# pulsePreamplifier.net
KiCad netlist of a schematic drawn in Altium Designer
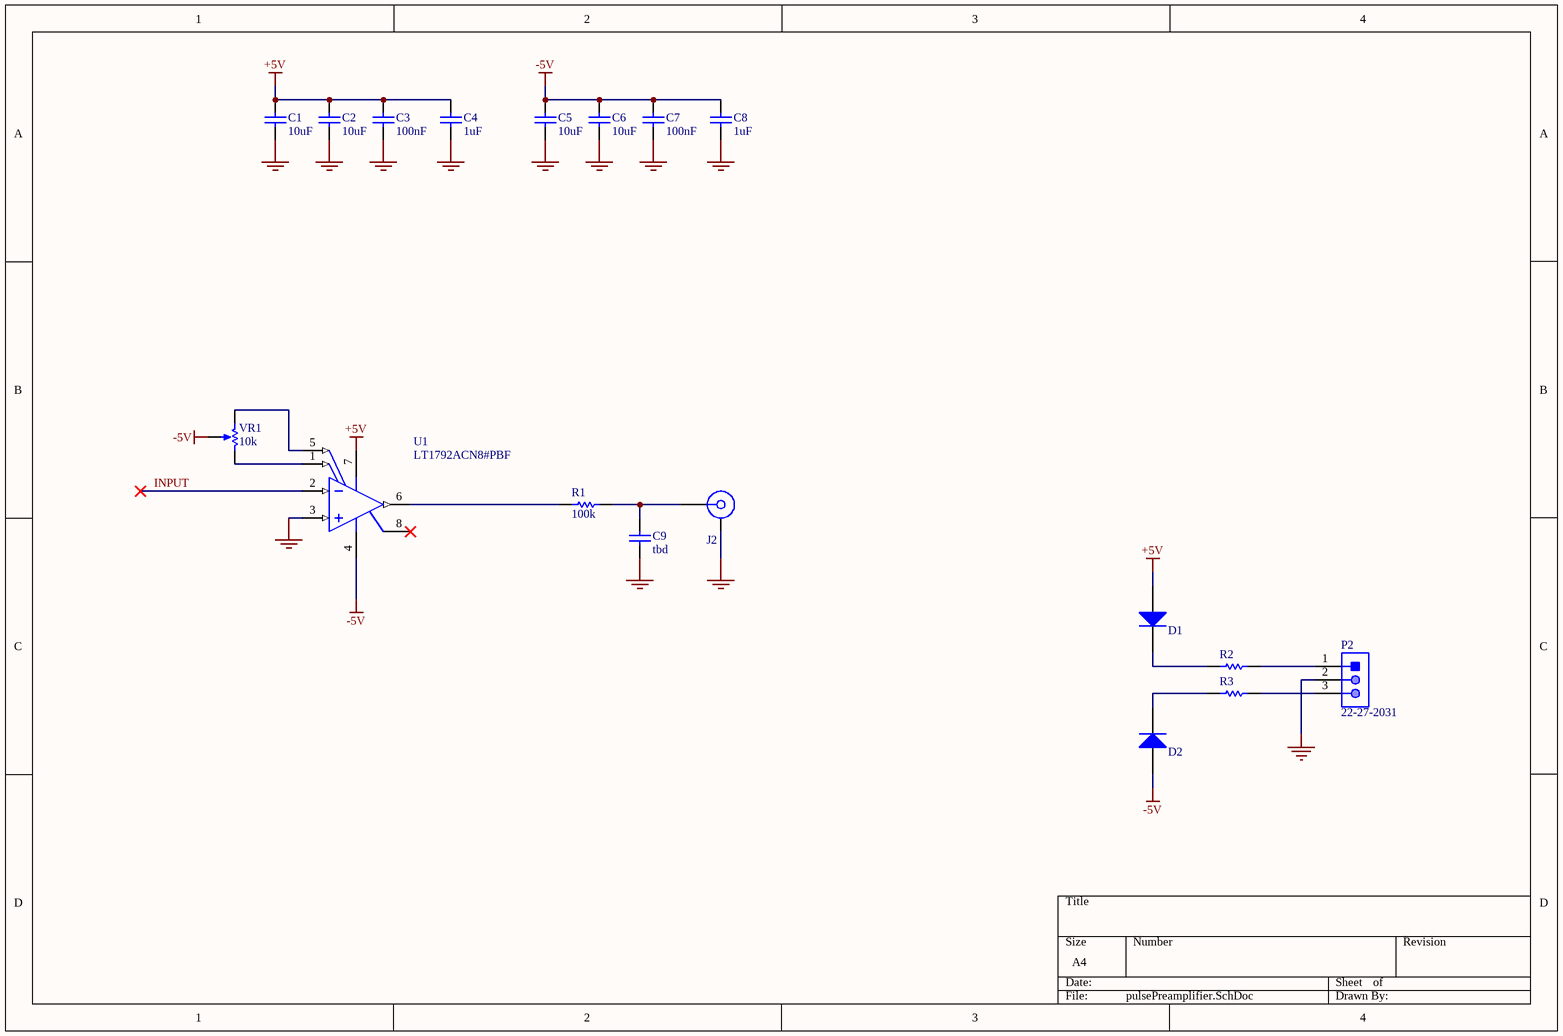
[diagram p0: pulsePreamplifier.SchDoc]

(export (version "E")
  (design (tool "Eeschema 10.0.6"))
  (components
    (comp (ref "C1")
      (value "10uF")
      (footprint "CAPC1206(3216)130_L")
      (description "CAP 10uF 10V -20% to +80% 1206 (3216 Metric) Thickness 1.3mm SMD")
      (fields (field (name "TOLERANCE") "-20% to +80%"))
      (libsource (lib "Altium Content Vault") (part "CAP"))
    )
    (comp (ref "C2")
      (value "10uF")
      (footprint "CAPC1206(3216)130_L")
      (description "CAP 10uF 10V -20% to +80% 1206 (3216 Metric) Thickness 1.3mm SMD")
      (fields (field (name "TOLERANCE") "-20% to +80%"))
      (libsource (lib "Altium Content Vault") (part "CAP"))
    )
    (comp (ref "C3")
      (value "100nF")
      (footprint "CAPC0603(1608)100_N")
      (description "CAP 100nF 25V ±20% 0603 (1608 Metric) Thickness 1mm SMD")
      (fields (field (name "TOLERANCE") "Â±20%"))
      (libsource (lib "Altium Content Vault") (part "CAP"))
    )
    (comp (ref "C4")
      (value "1uF")
      (footprint "CAPC0603(1608)100_N")
      (description "CAP 1uF 25V ±20% 0603 (1608 Metric) Thickness 1mm SMD")
      (fields (field (name "TOLERANCE") "Â±20%"))
      (libsource (lib "Altium Content Vault") (part "CAP"))
    )
    (comp (ref "C5")
      (value "10uF")
      (footprint "CAPC1206(3216)130_L")
      (description "CAP 10uF 10V -20% to +80% 1206 (3216 Metric) Thickness 1.3mm SMD")
      (fields (field (name "TOLERANCE") "-20% to +80%"))
      (libsource (lib "Altium Content Vault") (part "CAP"))
    )
    (comp (ref "C6")
      (value "10uF")
      (footprint "CAPC1206(3216)130_L")
      (description "CAP 10uF 10V -20% to +80% 1206 (3216 Metric) Thickness 1.3mm SMD")
      (fields (field (name "TOLERANCE") "-20% to +80%"))
      (libsource (lib "Altium Content Vault") (part "CAP"))
    )
    (comp (ref "C7")
      (value "100nF")
      (footprint "CAPC0603(1608)100_N")
      (description "CAP 100nF 25V ±20% 0603 (1608 Metric) Thickness 1mm SMD")
      (fields (field (name "TOLERANCE") "Â±20%"))
      (libsource (lib "Altium Content Vault") (part "CAP"))
    )
    (comp (ref "C8")
      (value "1uF")
      (footprint "CAPC0603(1608)100_N")
      (description "CAP 1uF 25V ±20% 0603 (1608 Metric) Thickness 1mm SMD")
      (fields (field (name "TOLERANCE") "Â±20%"))
      (libsource (lib "Altium Content Vault") (part "CAP"))
    )
    (comp (ref "C9")
      (value "tbd")
      (footprint "CAPC0603(1608)100_N")
      (description "CAP 1uF 25V ±20% 0603 (1608 Metric) Thickness 1mm SMD")
      (fields (field (name "TOLERANCE") "Â±20%"))
      (libsource (lib "Altium Content Vault") (part "CAP"))
    )
    (comp (ref "D1")
      (value "MMSD4148T3G")
      (footprint "ONSC-SOD123-2-425G-04_V")
      (description "Switching Diode, 100 V, 200 mA, -55 to 150 degC, 2-Pin SOD123 (425), RoHS, Tape and Reel")
      (fields (field (name "MANUFACTURER") "ON Semiconductor"))
      (libsource (lib "Altium Content Vault") (part "ONSC-MMSD4148-SOD123-2"))
    )
    (comp (ref "D2")
      (value "MMSD4148T3G")
      (footprint "ONSC-SOD123-2-425G-04_V")
      (description "Switching Diode, 100 V, 200 mA, -55 to 150 degC, 2-Pin SOD123 (425), RoHS, Tape and Reel")
      (fields (field (name "MANUFACTURER") "ON Semiconductor"))
      (libsource (lib "Altium Content Vault") (part "ONSC-MMSD4148-SOD123-2"))
    )
    (comp (ref "J2")
      (value "32K145-400L5")
      (footprint "ROS-32K145-400L5_V")
      (description "SMA Right Angle Jack, Edge Mount, Up to 18 GHz, -55 to 155 degC")
      (fields (field (name "MANUFACTURER") "Rosenberger"))
      (libsource (lib "Altium Content Vault") (part "ROS-CN-1F-RF1-A"))
    )
    (comp (ref "P2")
      (value "22-27-2031")
      (footprint "MOLX-22-27-2031_V")
      (fields (field (name "MANUFACTURER") "Molex"))
      (libsource (lib "Altium Content Vault") (part "CN-1P-M-R3"))
    )
    (comp (ref "R1")
      (value "100k")
      (footprint "RESC0805(2012)_L")
      (fields (field (name "TOLERANCE") "1 %") (field (name "POWER") "0.125 W"))
      (libsource (lib "Altium Content Vault") (part "RES"))
    )
    (comp (ref "R2")
      (value "100k")
      (footprint "RESC0603(1608)_N")
      (description "100R 0.1W 1% 0603 (1608 Metric)  SMD")
      (fields (field (name "TOLERANCE") "1 %") (field (name "POWER") "0.1 W"))
      (libsource (lib "Altium Content Vault") (part "RES"))
    )
    (comp (ref "R3")
      (value "100k")
      (footprint "RESC0603(1608)_N")
      (description "100R 0.1W 1% 0603 (1608 Metric)  SMD")
      (fields (field (name "TOLERANCE") "1 %") (field (name "POWER") "0.1 W"))
      (libsource (lib "Altium Content Vault") (part "RES"))
    )
    (comp (ref "U1")
      (value "LT1792ACN8#PBF")
      (footprint "LT-N8-8")
      (fields
        (field (name "MANUFACTURER") "Linear Technology")
        (field (name "LINEAR TECHNOLOGY PART NUMBER") "LT1792")
      )
      (libsource (lib "Altium Content Vault") (part "LT-LT1792-N8-8"))
    )
    (comp (ref "VR1")
      (value "10k")
      (footprint "BOUR-3362P")
      (description "Square Trimpot(R) Trimming Potentiometer, 10 KOhm, 300 V, -55 to 125 degC, 3-Pin THD, RoHS, Tube")
      (fields (field (name "TOLERANCE") "1%"))
      (libsource (lib "Altium Content Vault") (part "RES-POT-3"))
    )
  )
  (nets
    (net (code "1") (name "+5V") (class "Default")
      (node (ref "C1") (pin "2") (pinfunction "2_2") (pintype "passive"))
      (node (ref "C2") (pin "2") (pinfunction "2_2") (pintype "passive"))
      (node (ref "C3") (pin "2") (pinfunction "2_2") (pintype "passive"))
      (node (ref "C4") (pin "2") (pinfunction "2_2") (pintype "passive"))
      (node (ref "D1") (pin "2") (pinfunction "ANODE_2") (pintype "passive"))
      (node (ref "U1") (pin "7") (pinfunction "V+_7") (pintype "power_in"))
    )
    (net (code "2") (name "-5V") (class "Default")
      (node (ref "C5") (pin "2") (pinfunction "2_2") (pintype "passive"))
      (node (ref "C6") (pin "2") (pinfunction "2_2") (pintype "passive"))
      (node (ref "C7") (pin "2") (pinfunction "2_2") (pintype "passive"))
      (node (ref "C8") (pin "2") (pinfunction "2_2") (pintype "passive"))
      (node (ref "D2") (pin "2") (pinfunction "ANODE_2") (pintype "passive"))
      (node (ref "U1") (pin "4") (pinfunction "V-_4") (pintype "power_in"))
      (node (ref "VR1") (pin "2") (pinfunction "S_2") (pintype "passive"))
    )
    (net (code "3") (name "/INPUT") (class "Default")
      (node (ref "U1") (pin "2") (pinfunction "-IN_A_2") (pintype "input+no_connect"))
    )
    (net (code "4") (name "GND") (class "Default")
      (node (ref "C1") (pin "1") (pinfunction "1_1") (pintype "passive"))
      (node (ref "C2") (pin "1") (pinfunction "1_1") (pintype "passive"))
      (node (ref "C3") (pin "1") (pinfunction "1_1") (pintype "passive"))
      (node (ref "C4") (pin "1") (pinfunction "1_1") (pintype "passive"))
      (node (ref "C5") (pin "1") (pinfunction "1_1") (pintype "passive"))
      (node (ref "C6") (pin "1") (pinfunction "1_1") (pintype "passive"))
      (node (ref "C7") (pin "1") (pinfunction "1_1") (pintype "passive"))
      (node (ref "C8") (pin "1") (pinfunction "1_1") (pintype "passive"))
      (node (ref "C9") (pin "2") (pinfunction "2_2") (pintype "passive"))
      (node (ref "J2") (pin "MP") (pinfunction "MP_MP") (pintype "passive"))
      (node (ref "P2") (pin "2") (pinfunction "2_2") (pintype "passive"))
      (node (ref "U1") (pin "3") (pinfunction "+IN_A_3") (pintype "input"))
    )
    (net (code "5") (name "Net-(C9-Pad1)") (class "Default")
      (node (ref "C9") (pin "1") (pinfunction "1_1") (pintype "passive"))
      (node (ref "J2") (pin "1") (pinfunction "1_1") (pintype "passive"))
      (node (ref "R1") (pin "1") (pinfunction "1_1") (pintype "passive"))
    )
    (net (code "6") (name "Net-(D1-CATHODE)") (class "Default")
      (node (ref "D1") (pin "1") (pinfunction "CATHODE_1") (pintype "passive"))
      (node (ref "R2") (pin "2") (pinfunction "2_2") (pintype "passive"))
    )
    (net (code "7") (name "Net-(D2-CATHODE)") (class "Default")
      (node (ref "D2") (pin "1") (pinfunction "CATHODE_1") (pintype "passive"))
      (node (ref "R3") (pin "2") (pinfunction "2_2") (pintype "passive"))
    )
    (net (code "8") (name "Net-(P2-Pad1)") (class "Default")
      (node (ref "P2") (pin "1") (pinfunction "1_1") (pintype "passive"))
      (node (ref "R2") (pin "1") (pinfunction "1_1") (pintype "passive"))
    )
    (net (code "9") (name "Net-(P2-Pad3)") (class "Default")
      (node (ref "P2") (pin "3") (pinfunction "3_3") (pintype "passive"))
      (node (ref "R3") (pin "1") (pinfunction "1_1") (pintype "passive"))
    )
    (net (code "10") (name "Net-(U1-OUT)") (class "Default")
      (node (ref "R1") (pin "2") (pinfunction "2_2") (pintype "passive"))
      (node (ref "U1") (pin "6") (pinfunction "OUT_6") (pintype "output"))
    )
    (net (code "11") (name "Net-(VR1-CCW)") (class "Default")
      (node (ref "U1") (pin "1") (pinfunction "VOS_ADJ_1") (pintype "input"))
      (node (ref "VR1") (pin "1") (pinfunction "CCW_1") (pintype "passive"))
    )
    (net (code "12") (name "Net-(VR1-CW)") (class "Default")
      (node (ref "U1") (pin "5") (pinfunction "VOS_ADJ_5") (pintype "input"))
      (node (ref "VR1") (pin "3") (pinfunction "CW_3") (pintype "passive"))
    )
    (net (code "13") (name "unconnected-(U1-NC-Pad8)") (class "Default")
      (node (ref "U1") (pin "8") (pinfunction "NC_8") (pintype "passive+no_connect"))
    )
  )
)
